# board2.net
KiCad netlist of a schematic drawn in EAGLE
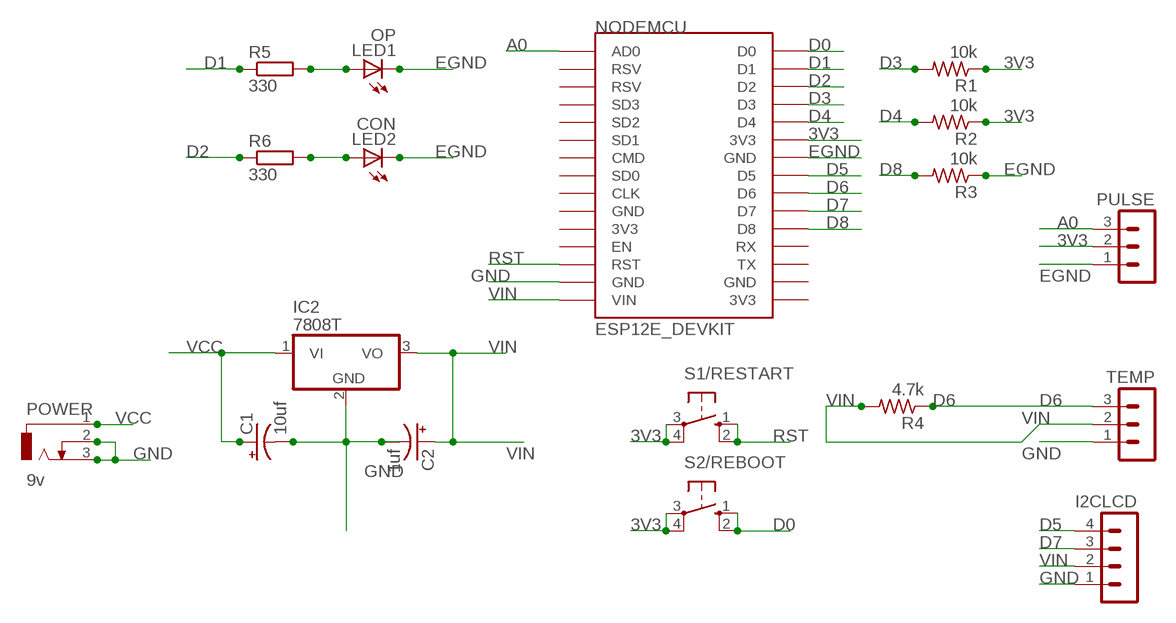
[diagram p0: schematic, sheet 1]

(export (version "E")
  (design (tool "Eeschema 10.0.6"))
  (components
    (comp (ref "C1")
      (value "10uf")
      (footprint "eagle-import:E2,5-5")
      (libsource (lib "eagle-import") (part "CPOL-USE2.5-5"))
    )
    (comp (ref "C2")
      (value "1uf")
      (footprint "eagle-import:E2,5-5")
      (libsource (lib "eagle-import") (part "CPOL-USE2.5-5"))
    )
    (comp (ref "I2CLCD")
      (value "MA04-1")
      (footprint "eagle-import:MA04-1")
      (libsource (lib "eagle-import") (part "MA04-1"))
    )
    (comp (ref "IC2")
      (value "7808T")
      (footprint "eagle-import:TO220H")
      (libsource (lib "eagle-import") (part "78T08"))
    )
    (comp (ref "LED1")
      (value "OP")
      (footprint "eagle-import:LED3MM")
      (fields (field (name "MF") "VISHAY SEMICONDUCTOR"))
      (libsource (lib "eagle-import") (part "TLLG4400"))
    )
    (comp (ref "LED2")
      (value "CON")
      (footprint "eagle-import:LED3MM")
      (fields (field (name "MF") "VISHAY SEMICONDUCTOR"))
      (libsource (lib "eagle-import") (part "TLLR4400"))
    )
    (comp (ref "NODEMCU")
      (value "ESP12E_DEVKIT")
      (footprint "eagle-import:ESP12E_DEVKIT")
      (libsource (lib "eagle-import") (part "ESP12E_DEVKIT"))
    )
    (comp (ref "POWER")
      (value "9v")
      (footprint "eagle-import:DCJ0303")
      (libsource (lib "eagle-import") (part "DCJ0303"))
    )
    (comp (ref "PULSE")
      (value "MA03-1")
      (footprint "eagle-import:MA03-1")
      (libsource (lib "eagle-import") (part "MA03-1"))
    )
    (comp (ref "R1")
      (value "10k")
      (footprint "eagle-import:0207_7")
      (libsource (lib "eagle-import") (part "R-US_0207/7"))
    )
    (comp (ref "R2")
      (value "10k")
      (footprint "eagle-import:0207_7")
      (libsource (lib "eagle-import") (part "resistor_R-US_0207/7"))
    )
    (comp (ref "R3")
      (value "10k")
      (footprint "eagle-import:0207_7")
      (libsource (lib "eagle-import") (part "R-US_0207/7"))
    )
    (comp (ref "R4")
      (value "4.7k")
      (footprint "eagle-import:0207_7")
      (libsource (lib "eagle-import") (part "resistor_R-US_0207/7"))
    )
    (comp (ref "R5")
      (value "330")
      (footprint "eagle-import:0204_5")
      (libsource (lib "eagle-import") (part "R-EU_0204/5"))
    )
    (comp (ref "R6")
      (value "330")
      (footprint "eagle-import:0204_5")
      (libsource (lib "eagle-import") (part "R-EU_0204/5"))
    )
    (comp (ref "S1/RESTART")
      (value "10-XX")
      (footprint "eagle-import:B3F-10XX")
      (fields (field (name "MPN") "B3F-1000"))
      (libsource (lib "eagle-import") (part "10-XX"))
    )
    (comp (ref "S2/REBOOT")
      (value "10-XX")
      (footprint "eagle-import:B3F-10XX")
      (fields (field (name "MPN") "B3F-1000"))
      (libsource (lib "eagle-import") (part "10-XX"))
    )
    (comp (ref "TEMP")
      (value "MA03-1")
      (footprint "eagle-import:MA03-1")
      (libsource (lib "eagle-import") (part "MA03-1"))
    )
  )
  (nets
    (net (code "1") (name "/3V3") (class "Default")
      (node (ref "NODEMCU") (pin "3V3@1") (pinfunction "3V3_3V3@1") (pintype "bidirectional"))
      (node (ref "PULSE") (pin "2") (pinfunction "2_2") (pintype "passive"))
      (node (ref "R1") (pin "1") (pinfunction "1_1") (pintype "passive"))
      (node (ref "R2") (pin "1") (pinfunction "1_1") (pintype "passive"))
      (node (ref "S1/RESTART") (pin "3") (pinfunction "P_3") (pintype "passive"))
      (node (ref "S1/RESTART") (pin "4") (pinfunction "P1_4") (pintype "passive"))
      (node (ref "S2/REBOOT") (pin "3") (pinfunction "P_3") (pintype "passive"))
      (node (ref "S2/REBOOT") (pin "4") (pinfunction "P1_4") (pintype "passive"))
    )
    (net (code "2") (name "/A0") (class "Default")
      (node (ref "NODEMCU") (pin "AD0") (pinfunction "AD0_AD0") (pintype "bidirectional"))
      (node (ref "PULSE") (pin "3") (pinfunction "3_3") (pintype "passive"))
    )
    (net (code "3") (name "/D0") (class "Default")
      (node (ref "NODEMCU") (pin "D0") (pinfunction "D0_D0") (pintype "bidirectional"))
      (node (ref "S2/REBOOT") (pin "1") (pinfunction "S_1") (pintype "passive"))
      (node (ref "S2/REBOOT") (pin "2") (pinfunction "S1_2") (pintype "passive"))
    )
    (net (code "4") (name "/D1") (class "Default")
      (node (ref "NODEMCU") (pin "D1") (pinfunction "D1_D1") (pintype "bidirectional"))
      (node (ref "R5") (pin "1") (pinfunction "1_1") (pintype "passive"))
    )
    (net (code "5") (name "/D2") (class "Default")
      (node (ref "NODEMCU") (pin "D2") (pinfunction "D2_D2") (pintype "bidirectional"))
      (node (ref "R6") (pin "1") (pinfunction "1_1") (pintype "passive"))
    )
    (net (code "6") (name "/D3") (class "Default")
      (node (ref "NODEMCU") (pin "D3") (pinfunction "D3_D3") (pintype "bidirectional"))
      (node (ref "R1") (pin "2") (pinfunction "2_2") (pintype "passive"))
    )
    (net (code "7") (name "/D4") (class "Default")
      (node (ref "NODEMCU") (pin "D4") (pinfunction "D4_D4") (pintype "bidirectional"))
      (node (ref "R2") (pin "2") (pinfunction "2_2") (pintype "passive"))
    )
    (net (code "8") (name "/D5") (class "Default")
      (node (ref "I2CLCD") (pin "4") (pinfunction "4_4") (pintype "passive"))
      (node (ref "NODEMCU") (pin "D5") (pinfunction "D5_D5") (pintype "bidirectional"))
    )
    (net (code "9") (name "/D6") (class "Default")
      (node (ref "NODEMCU") (pin "D6") (pinfunction "D6_D6") (pintype "bidirectional"))
      (node (ref "R4") (pin "1") (pinfunction "1_1") (pintype "passive"))
      (node (ref "TEMP") (pin "3") (pinfunction "3_3") (pintype "passive"))
    )
    (net (code "10") (name "/D7") (class "Default")
      (node (ref "I2CLCD") (pin "3") (pinfunction "3_3") (pintype "passive"))
      (node (ref "NODEMCU") (pin "D7") (pinfunction "D7_D7") (pintype "bidirectional"))
    )
    (net (code "11") (name "/D8") (class "Default")
      (node (ref "NODEMCU") (pin "D8") (pinfunction "D8_D8") (pintype "bidirectional"))
      (node (ref "R3") (pin "2") (pinfunction "2_2") (pintype "passive"))
    )
    (net (code "12") (name "/EGND") (class "Default")
      (node (ref "LED1") (pin "K") (pinfunction "C_K") (pintype "passive"))
      (node (ref "LED2") (pin "K") (pinfunction "C_K") (pintype "passive"))
      (node (ref "NODEMCU") (pin "GND@2") (pinfunction "GND_GND@2") (pintype "bidirectional"))
      (node (ref "PULSE") (pin "1") (pinfunction "1_1") (pintype "passive"))
      (node (ref "R3") (pin "1") (pinfunction "1_1") (pintype "passive"))
    )
    (net (code "13") (name "/GND") (class "Default")
      (node (ref "C1") (pin "-") (pinfunction "-_-") (pintype "passive"))
      (node (ref "C2") (pin "-") (pinfunction "-_-") (pintype "passive"))
      (node (ref "I2CLCD") (pin "1") (pinfunction "1_1") (pintype "passive"))
      (node (ref "IC2") (pin "2") (pinfunction "GND_2") (pintype "passive"))
      (node (ref "NODEMCU") (pin "GND@1") (pinfunction "GND_GND@1") (pintype "bidirectional"))
      (node (ref "POWER") (pin "2") (pinfunction "2_2") (pintype "passive"))
      (node (ref "POWER") (pin "3") (pinfunction "3_3") (pintype "passive"))
      (node (ref "TEMP") (pin "1") (pinfunction "1_1") (pintype "passive"))
    )
    (net (code "14") (name "/RST") (class "Default")
      (node (ref "NODEMCU") (pin "RST") (pinfunction "RST_RST") (pintype "bidirectional"))
      (node (ref "S1/RESTART") (pin "1") (pinfunction "S_1") (pintype "passive"))
      (node (ref "S1/RESTART") (pin "2") (pinfunction "S1_2") (pintype "passive"))
    )
    (net (code "15") (name "/VCC") (class "Default")
      (node (ref "C1") (pin "+") (pinfunction "+_+") (pintype "passive"))
      (node (ref "IC2") (pin "1") (pinfunction "VI_1") (pintype "input"))
      (node (ref "POWER") (pin "1") (pinfunction "1_1") (pintype "passive"))
    )
    (net (code "16") (name "/VIN") (class "Default")
      (node (ref "C2") (pin "+") (pinfunction "+_+") (pintype "passive"))
      (node (ref "I2CLCD") (pin "2") (pinfunction "2_2") (pintype "passive"))
      (node (ref "IC2") (pin "3") (pinfunction "VO_3") (pintype "passive"))
      (node (ref "NODEMCU") (pin "VIN") (pinfunction "VIN_VIN") (pintype "bidirectional"))
      (node (ref "R4") (pin "2") (pinfunction "2_2") (pintype "passive"))
      (node (ref "TEMP") (pin "2") (pinfunction "2_2") (pintype "passive"))
    )
    (net (code "17") (name "Net-(LED1-PadA)") (class "Default")
      (node (ref "LED1") (pin "A") (pinfunction "A_A") (pintype "passive"))
      (node (ref "R5") (pin "2") (pinfunction "2_2") (pintype "passive"))
    )
    (net (code "18") (name "Net-(LED2-PadA)") (class "Default")
      (node (ref "LED2") (pin "A") (pinfunction "A_A") (pintype "passive"))
      (node (ref "R6") (pin "2") (pinfunction "2_2") (pintype "passive"))
    )
    (net (code "19") (name "unconnected-(NODEMCU-3V3-Pad3V3@0)") (class "Default")
      (node (ref "NODEMCU") (pin "3V3@0") (pinfunction "3V3_3V3@0") (pintype "bidirectional"))
    )
    (net (code "20") (name "unconnected-(NODEMCU-3V3-Pad3V3@2)") (class "Default")
      (node (ref "NODEMCU") (pin "3V3@2") (pinfunction "3V3_3V3@2") (pintype "bidirectional"))
    )
    (net (code "21") (name "unconnected-(NODEMCU-GND-PadGND@0)") (class "Default")
      (node (ref "NODEMCU") (pin "GND@0") (pinfunction "GND_GND@0") (pintype "bidirectional"))
    )
    (net (code "22") (name "unconnected-(NODEMCU-GND-PadGND@3)") (class "Default")
      (node (ref "NODEMCU") (pin "GND@3") (pinfunction "GND_GND@3") (pintype "bidirectional"))
    )
    (net (code "23") (name "unconnected-(NODEMCU-PadCLK)") (class "Default")
      (node (ref "NODEMCU") (pin "CLK") (pinfunction "CLK_CLK") (pintype "bidirectional"))
    )
    (net (code "24") (name "unconnected-(NODEMCU-PadCMD)") (class "Default")
      (node (ref "NODEMCU") (pin "CMD") (pinfunction "CMD_CMD") (pintype "bidirectional"))
    )
    (net (code "25") (name "unconnected-(NODEMCU-PadEN)") (class "Default")
      (node (ref "NODEMCU") (pin "EN") (pinfunction "EN_EN") (pintype "bidirectional"))
    )
    (net (code "26") (name "unconnected-(NODEMCU-PadRX)") (class "Default")
      (node (ref "NODEMCU") (pin "RX") (pinfunction "RX_RX") (pintype "bidirectional"))
    )
    (net (code "27") (name "unconnected-(NODEMCU-PadSD0)") (class "Default")
      (node (ref "NODEMCU") (pin "SD0") (pinfunction "SD0_SD0") (pintype "bidirectional"))
    )
    (net (code "28") (name "unconnected-(NODEMCU-PadSD1)") (class "Default")
      (node (ref "NODEMCU") (pin "SD1") (pinfunction "SD1_SD1") (pintype "bidirectional"))
    )
    (net (code "29") (name "unconnected-(NODEMCU-PadSD2)") (class "Default")
      (node (ref "NODEMCU") (pin "SD2") (pinfunction "SD2_SD2") (pintype "bidirectional"))
    )
    (net (code "30") (name "unconnected-(NODEMCU-PadSD3)") (class "Default")
      (node (ref "NODEMCU") (pin "SD3") (pinfunction "SD3_SD3") (pintype "bidirectional"))
    )
    (net (code "31") (name "unconnected-(NODEMCU-PadTX)") (class "Default")
      (node (ref "NODEMCU") (pin "TX") (pinfunction "TX_TX") (pintype "bidirectional"))
    )
    (net (code "32") (name "unconnected-(NODEMCU-RSV-PadRSV@0)") (class "Default")
      (node (ref "NODEMCU") (pin "RSV@0") (pinfunction "RSV_RSV@0") (pintype "bidirectional"))
    )
    (net (code "33") (name "unconnected-(NODEMCU-RSV-PadRSV@1)") (class "Default")
      (node (ref "NODEMCU") (pin "RSV@1") (pinfunction "RSV_RSV@1") (pintype "bidirectional"))
    )
  )
)
